# CPS2_CN2_Adapter_V1_1.net
KiCad netlist of a schematic drawn in EAGLE
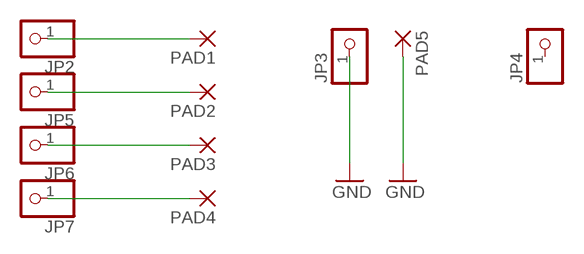
[diagram p0: schematic, sheet 1]

(export (version "E")
  (design (tool "Eeschema 10.0.6"))
  (components
    (comp (ref "JP2")
      (value "PINHD-1X1")
      (footprint "eagle-import:1X01")
      (libsource (lib "eagle-import") (part "PINHD-1X1"))
    )
    (comp (ref "JP3")
      (value "PINHD-1X1")
      (footprint "eagle-import:1X01")
      (libsource (lib "eagle-import") (part "PINHD-1X1"))
    )
    (comp (ref "JP4")
      (value "PINHD-1X1")
      (footprint "eagle-import:1X01")
      (libsource (lib "eagle-import") (part "PINHD-1X1"))
    )
    (comp (ref "JP5")
      (value "PINHD-1X1")
      (footprint "eagle-import:1X01")
      (libsource (lib "eagle-import") (part "PINHD-1X1"))
    )
    (comp (ref "JP6")
      (value "PINHD-1X1")
      (footprint "eagle-import:1X01")
      (libsource (lib "eagle-import") (part "PINHD-1X1"))
    )
    (comp (ref "JP7")
      (value "PINHD-1X1")
      (footprint "eagle-import:1X01")
      (libsource (lib "eagle-import") (part "PINHD-1X1"))
    )
    (comp (ref "PAD1")
      (value "SMD2")
      (footprint "eagle-import:SMD1,27-2,54")
      (libsource (lib "eagle-import") (part "SMD2"))
    )
    (comp (ref "PAD2")
      (value "SMD2")
      (footprint "eagle-import:SMD1,27-2,54")
      (libsource (lib "eagle-import") (part "SMD2"))
    )
    (comp (ref "PAD3")
      (value "SMD2")
      (footprint "eagle-import:SMD1,27-2,54")
      (libsource (lib "eagle-import") (part "SMD2"))
    )
    (comp (ref "PAD4")
      (value "SMD2")
      (footprint "eagle-import:SMD1,27-2,54")
      (libsource (lib "eagle-import") (part "SMD2"))
    )
    (comp (ref "PAD5")
      (value "SMD2")
      (footprint "eagle-import:SMD1,27-2,54")
      (libsource (lib "eagle-import") (part "SMD2"))
    )
  )
  (nets
    (net (code "1") (name "GND") (class "Default")
      (node (ref "JP3") (pin "1") (pinfunction "1_1") (pintype "passive"))
      (node (ref "PAD5") (pin "1") (pinfunction "P_1") (pintype "passive"))
    )
    (net (code "2") (name "Net-(PAD1-P)") (class "Default")
      (node (ref "JP2") (pin "1") (pinfunction "1_1") (pintype "passive"))
      (node (ref "PAD1") (pin "1") (pinfunction "P_1") (pintype "passive"))
    )
    (net (code "3") (name "Net-(PAD2-P)") (class "Default")
      (node (ref "JP5") (pin "1") (pinfunction "1_1") (pintype "passive"))
      (node (ref "PAD2") (pin "1") (pinfunction "P_1") (pintype "passive"))
    )
    (net (code "4") (name "Net-(PAD3-P)") (class "Default")
      (node (ref "JP6") (pin "1") (pinfunction "1_1") (pintype "passive"))
      (node (ref "PAD3") (pin "1") (pinfunction "P_1") (pintype "passive"))
    )
    (net (code "5") (name "Net-(PAD4-P)") (class "Default")
      (node (ref "JP7") (pin "1") (pinfunction "1_1") (pintype "passive"))
      (node (ref "PAD4") (pin "1") (pinfunction "P_1") (pintype "passive"))
    )
    (net (code "6") (name "unconnected-(JP4-Pad1)") (class "Default")
      (node (ref "JP4") (pin "1") (pinfunction "1_1") (pintype "passive"))
    )
  )
)
